# Schematic.net
KiCad netlist of a schematic drawn in Altium Designer
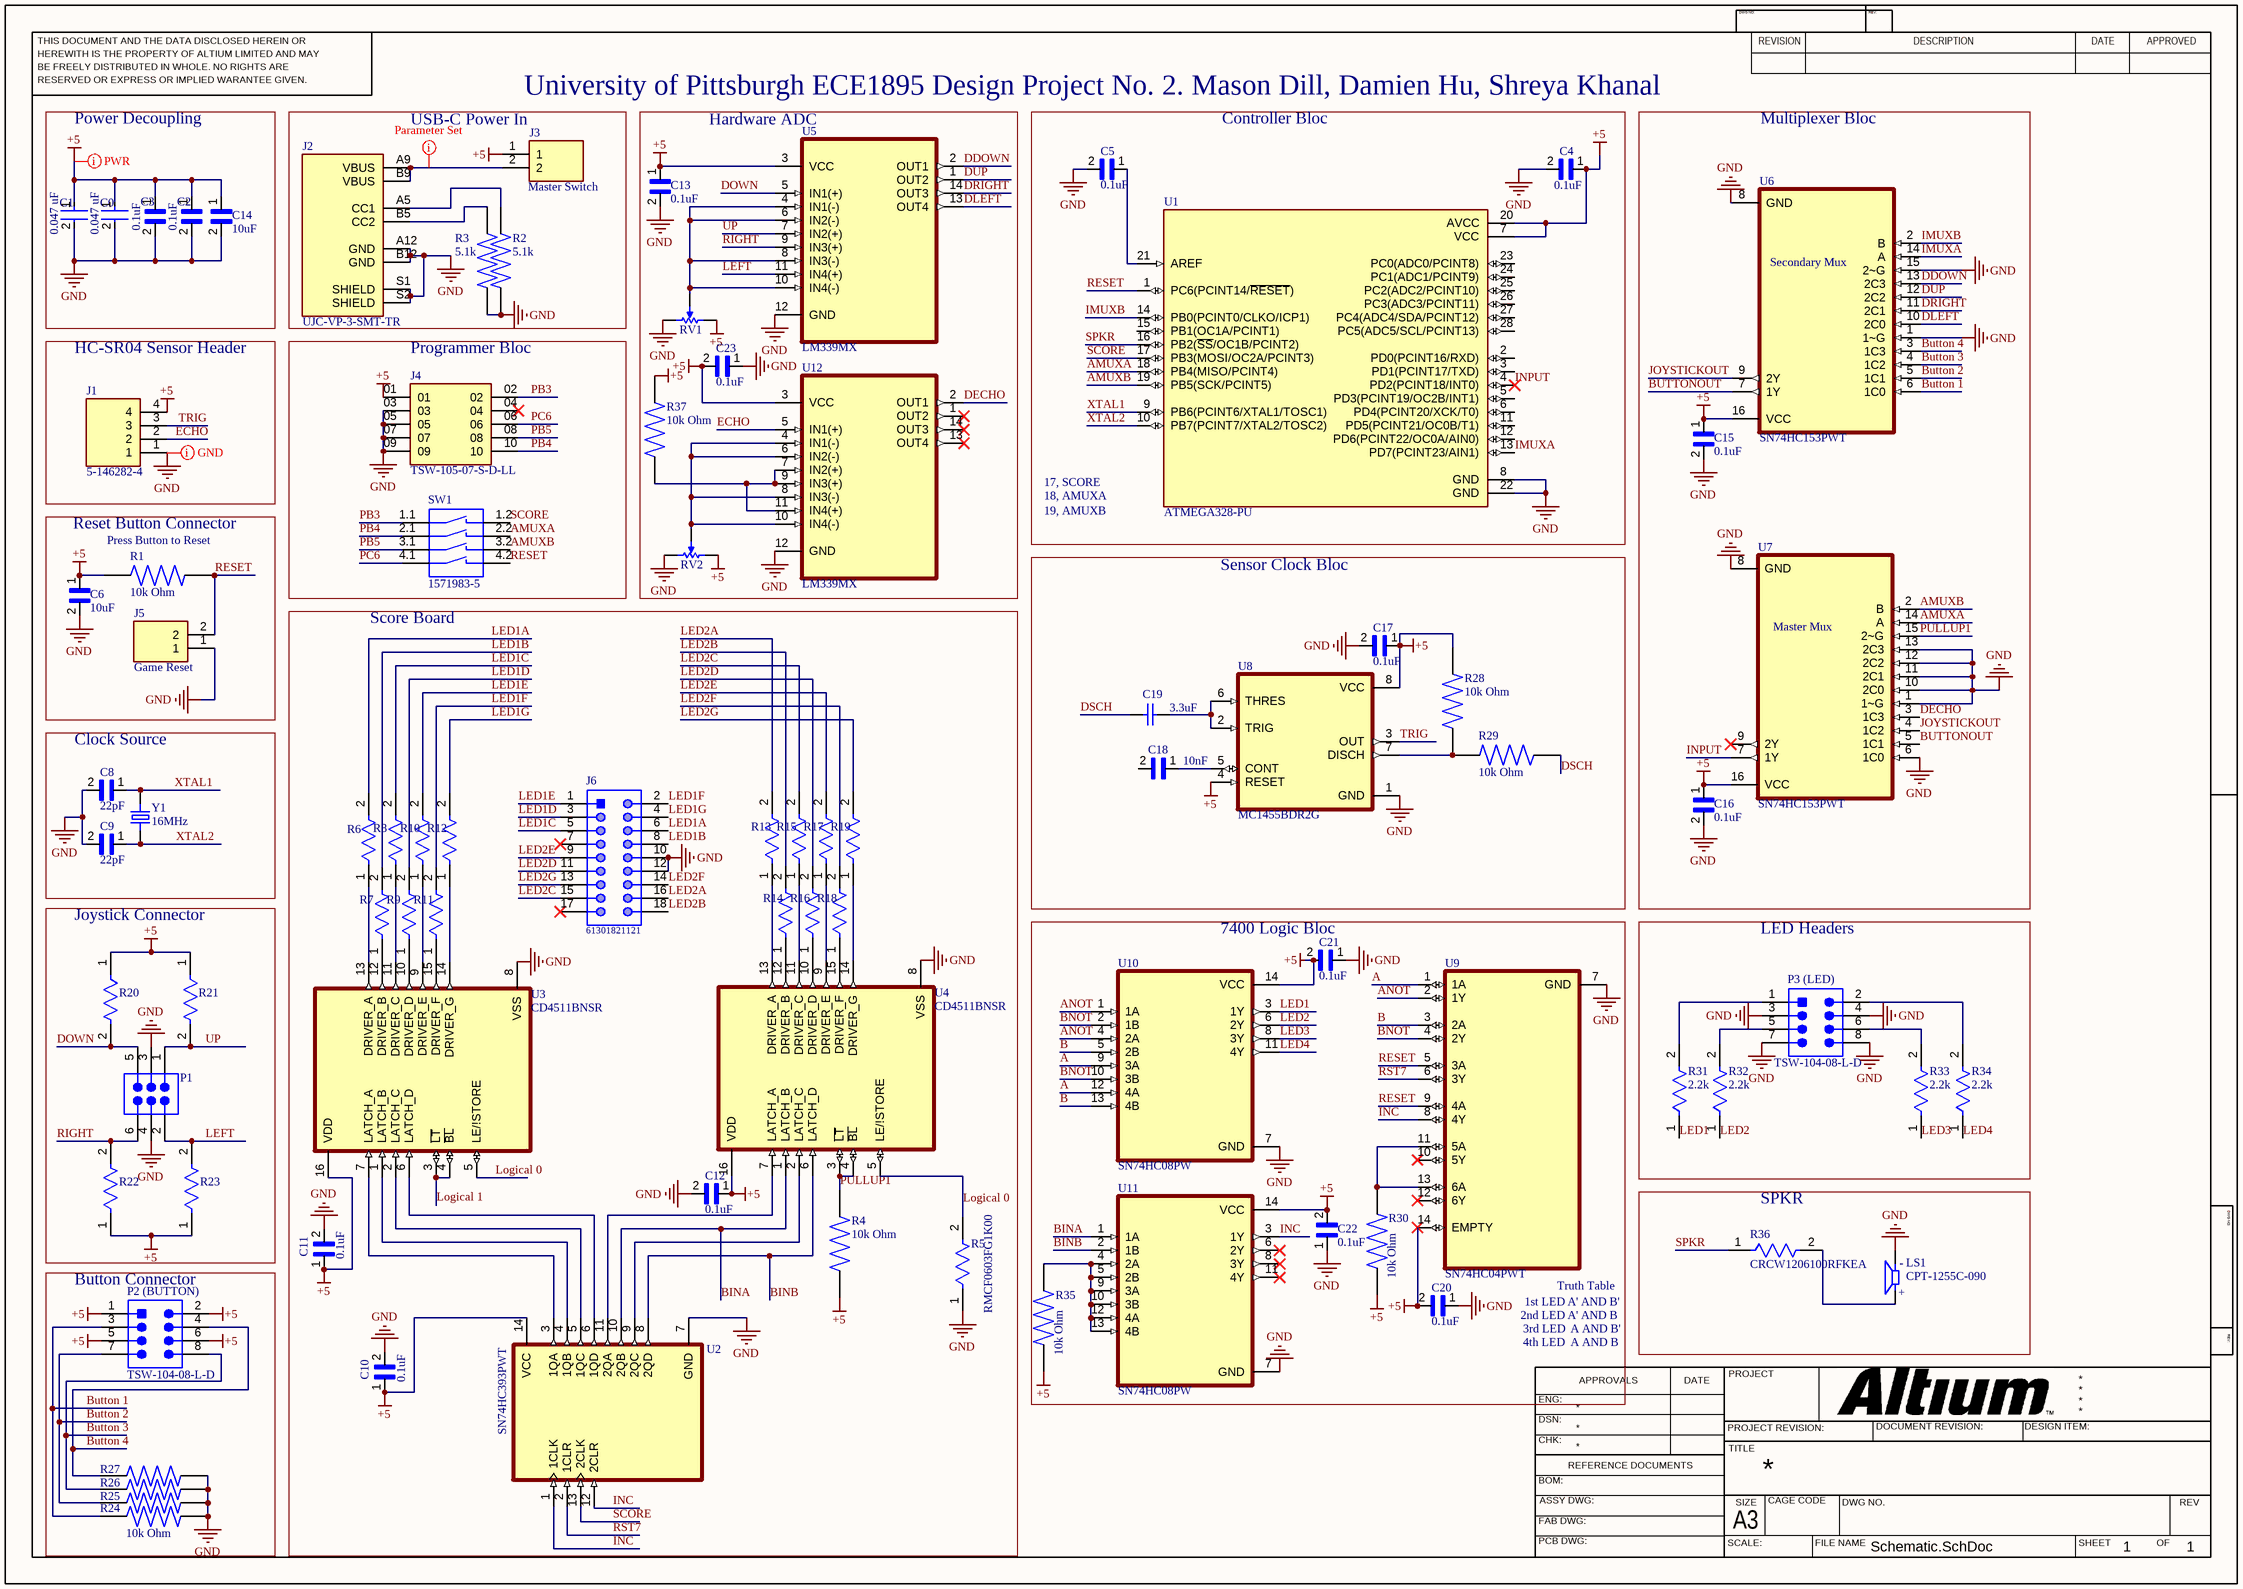
[diagram p0: Schematic.SchDoc]

(export (version "E")
  (design (tool "Eeschema 10.0.6"))
  (components
    (comp (ref "C0")
      (value "0.047 uF")
      (footprint "FP-C0603C-CF-MFG")
      (description "CAP CER 0.047UF 100V 5% X7R 0603")
      (fields
        (field (name "OCTOPART") "https://octopart.com/c0603c473j1ractu-kemet-17301356")
        (field (name "MANUFACTURER") "KEMET")
      )
      (libsource (lib "Altium Content Vault") (part "b4654b650e69147ec39a6b967a45e02"))
    )
    (comp (ref "C1")
      (value "0.047 uF")
      (footprint "FP-C0603C-CF-MFG")
      (description "CAP CER 0.047UF 100V 5% X7R 0603")
      (fields
        (field (name "OCTOPART") "https://octopart.com/c0603c473j1ractu-kemet-17301356")
        (field (name "MANUFACTURER") "KEMET")
      )
      (libsource (lib "Altium Content Vault") (part "b4654b650e69147ec39a6b967a45e02"))
    )
    (comp (ref "C2")
      (value "0.1uF")
      (footprint "CAPC1608X90N")
      (description "0.1ÂµF Â±10% 16V Ceramic Capacitor X7R 0603 _1608 Metric_")
      (fields (field (name "MF") "Taiyo Yuden") (field (name "DIGI-KEY_PART_NUMBER") "587-6004-1-ND"))
      (libsource (lib "") (part "EMK107B7104KAHT_1"))
    )
    (comp (ref "C3")
      (value "0.1uF")
      (footprint "CAPC1608X90N")
      (description "0.1ÂµF Â±10% 16V Ceramic Capacitor X7R 0603 _1608 Metric_")
      (fields (field (name "MF") "Taiyo Yuden") (field (name "DIGI-KEY_PART_NUMBER") "587-6004-1-ND"))
      (libsource (lib "") (part "EMK107B7104KAHT_1"))
    )
    (comp (ref "C4")
      (value "0.1uF")
      (footprint "CAPC1608X90N")
      (description "0.1ÂµF Â±10% 16V Ceramic Capacitor X7R 0603 _1608 Metric_")
      (fields (field (name "MF") "Taiyo Yuden") (field (name "DIGI-KEY_PART_NUMBER") "587-6004-1-ND"))
      (libsource (lib "EMK107B7104KAHT") (part "EMK107B7104KAHT"))
    )
    (comp (ref "C5")
      (value "0.1uF")
      (footprint "CAPC1608X90N")
      (description "0.1ÂµF Â±10% 16V Ceramic Capacitor X7R 0603 _1608 Metric_")
      (fields (field (name "MF") "Taiyo Yuden") (field (name "DIGI-KEY_PART_NUMBER") "587-6004-1-ND"))
      (libsource (lib "EMK107B7104KAHT") (part "EMK107B7104KAHT"))
    )
    (comp (ref "C6")
      (value "10uF")
      (footprint "CAPC1608X90N")
      (description "10 ÂµF Â±10% 10V Ceramic Capacitor JB 0603 (1608 Metric)")
      (fields (field (name "MP") "C1608JB1A106K080AC") (field (name "DIGI-KEY_PART_NUMBER") "445-11201-2-ND"))
      (libsource (lib "C1608JB1A106K080AC") (part "C1608JB1A106K080AC"))
    )
    (comp (ref "C8")
      (value "22pF")
      (footprint "CAPC1608X90N")
      (description "22pF Â±5% 25V Ceramic Capacitor C0G, NP0 0603 _1608 Metric_")
      (fields (field (name "MF") "KEMET") (field (name "MP") "C0603C220J3GACAUTO"))
      (libsource (lib "C0603C220J3GACAUTO") (part "C0603C220J3GACAUTO"))
    )
    (comp (ref "C9")
      (value "22pF")
      (footprint "CAPC1608X90N")
      (description "22pF Â±5% 25V Ceramic Capacitor C0G, NP0 0603 _1608 Metric_")
      (fields (field (name "MF") "KEMET") (field (name "MP") "C0603C220J3GACAUTO"))
      (libsource (lib "C0603C220J3GACAUTO") (part "C0603C220J3GACAUTO"))
    )
    (comp (ref "C10")
      (value "0.1uF")
      (footprint "CAPC1608X90N")
      (description "0.1ÂµF Â±10% 16V Ceramic Capacitor X7R 0603 _1608 Metric_")
      (fields (field (name "MF") "Taiyo Yuden") (field (name "DIGI-KEY_PART_NUMBER") "587-6004-1-ND"))
      (libsource (lib "") (part "EMK107B7104KAHT_2"))
    )
    (comp (ref "C11")
      (value "0.1uF")
      (footprint "CAPC1608X90N")
      (description "0.1ÂµF Â±10% 16V Ceramic Capacitor X7R 0603 _1608 Metric_")
      (fields (field (name "MF") "Taiyo Yuden") (field (name "DIGI-KEY_PART_NUMBER") "587-6004-1-ND"))
      (libsource (lib "") (part "EMK107B7104KAHT_2"))
    )
    (comp (ref "C12")
      (value "0.1uF")
      (footprint "CAPC1608X90N")
      (description "0.1ÂµF Â±10% 16V Ceramic Capacitor X7R 0603 _1608 Metric_")
      (fields (field (name "MF") "Taiyo Yuden") (field (name "DIGI-KEY_PART_NUMBER") "587-6004-1-ND"))
      (libsource (lib "EMK107B7104KAHT") (part "EMK107B7104KAHT"))
    )
    (comp (ref "C13")
      (value "0.1uF")
      (footprint "CAPC1608X90N")
      (description "0.1ÂµF Â±10% 16V Ceramic Capacitor X7R 0603 _1608 Metric_")
      (fields (field (name "MF") "Taiyo Yuden") (field (name "DIGI-KEY_PART_NUMBER") "587-6004-1-ND"))
      (libsource (lib "") (part "EMK107B7104KAHT_1"))
    )
    (comp (ref "C14")
      (value "10uF")
      (footprint "CAPC1608X90N")
      (description "10 ÂµF Â±10% 10V Ceramic Capacitor JB 0603 (1608 Metric)")
      (fields (field (name "MP") "C1608JB1A106K080AC") (field (name "DIGI-KEY_PART_NUMBER") "445-11201-2-ND"))
      (libsource (lib "C1608JB1A106K080AC") (part "C1608JB1A106K080AC"))
    )
    (comp (ref "C15")
      (value "0.1uF")
      (footprint "CAPC1608X90N")
      (description "0.1ÂµF Â±10% 16V Ceramic Capacitor X7R 0603 _1608 Metric_")
      (fields (field (name "MF") "Taiyo Yuden") (field (name "DIGI-KEY_PART_NUMBER") "587-6004-1-ND"))
      (libsource (lib "") (part "EMK107B7104KAHT_1"))
    )
    (comp (ref "C16")
      (value "0.1uF")
      (footprint "CAPC1608X90N")
      (description "0.1ÂµF Â±10% 16V Ceramic Capacitor X7R 0603 _1608 Metric_")
      (fields (field (name "MF") "Taiyo Yuden") (field (name "DIGI-KEY_PART_NUMBER") "587-6004-1-ND"))
      (libsource (lib "") (part "EMK107B7104KAHT_1"))
    )
    (comp (ref "C17")
      (value "0.1uF")
      (footprint "CAPC1608X90N")
      (description "0.1ÂµF Â±10% 16V Ceramic Capacitor X7R 0603 _1608 Metric_")
      (fields (field (name "MF") "Taiyo Yuden") (field (name "DIGI-KEY_PART_NUMBER") "587-6004-1-ND"))
      (libsource (lib "EMK107B7104KAHT") (part "EMK107B7104KAHT"))
    )
    (comp (ref "C18")
      (value "10nF")
      (footprint "CAPC2012X88N")
      (fields (field (name "MP") "C0805C103K1RECAUTO"))
      (libsource (lib "C0805C103K1RECAUTO") (part "C0805C103K1RECAUTO"))
    )
    (comp (ref "C19")
      (value "3.3uF")
      (footprint "CAPC1608X90X35NL15T15")
      (fields (field (name "PART NUMBER") "C0603C335M9PACTU") (field (name "MANUFACTURER") "Kemet"))
      (libsource (lib "Altium Content Vault") (part "CAP"))
    )
    (comp (ref "C20")
      (value "0.1uF")
      (footprint "CAPC1608X90N")
      (description "0.1ÂµF Â±10% 16V Ceramic Capacitor X7R 0603 _1608 Metric_")
      (fields (field (name "MF") "Taiyo Yuden") (field (name "DIGI-KEY_PART_NUMBER") "587-6004-1-ND"))
      (libsource (lib "EMK107B7104KAHT") (part "EMK107B7104KAHT"))
    )
    (comp (ref "C21")
      (value "0.1uF")
      (footprint "CAPC1608X90N")
      (description "0.1ÂµF Â±10% 16V Ceramic Capacitor X7R 0603 _1608 Metric_")
      (fields (field (name "MF") "Taiyo Yuden") (field (name "DIGI-KEY_PART_NUMBER") "587-6004-1-ND"))
      (libsource (lib "EMK107B7104KAHT") (part "EMK107B7104KAHT"))
    )
    (comp (ref "C22")
      (value "0.1uF")
      (footprint "CAPC1608X90N")
      (description "0.1ÂµF Â±10% 16V Ceramic Capacitor X7R 0603 _1608 Metric_")
      (fields (field (name "MF") "Taiyo Yuden") (field (name "DIGI-KEY_PART_NUMBER") "587-6004-1-ND"))
      (libsource (lib "") (part "EMK107B7104KAHT_2"))
    )
    (comp (ref "C23")
      (value "0.1uF")
      (footprint "CAPC1608X90N")
      (description "0.1ÂµF Â±10% 16V Ceramic Capacitor X7R 0603 _1608 Metric_")
      (fields (field (name "MF") "Taiyo Yuden") (field (name "DIGI-KEY_PART_NUMBER") "587-6004-1-ND"))
      (libsource (lib "EMK107B7104KAHT") (part "EMK107B7104KAHT"))
    )
    (comp (ref "J1")
      (value "5-146282-4")
      (footprint "TE_5-146282-4")
      (description "Connector Header Through Hole 4 position 0.100 (2.54mm)")
      (fields (field (name "MF") "TE Connectivity"))
      (libsource (lib "5-146282-4") (part "5-146282-4"))
    )
    (comp (ref "J2")
      (value "UJC-VP-3-SMT-TR")
      (footprint "CUI_UJC-VP-3-SMT-TR")
      (description "USB Receptacle")
      (fields (field (name "MF") "{'manufacturer': u'CUI'}"))
      (libsource (lib "UJC-VP-3-SMT-TR") (part "UJC-VP-3-SMT-TR"))
    )
    (comp (ref "J3")
      (value "Master Switch")
      (footprint "CUI_TB003-500-P02BE")
      (description "2~24 Poles, Screw Type, Horizontal, 5.0 Pitch, 26~14 _AWG_, Terminal Block Connector")
      (fields (field (name "MP") "TB003-500-P02BE") (field (name "MF") "CUI Devices"))
      (libsource (lib "TB003-500-P02BE") (part "TB003-500-P02BE"))
    )
    (comp (ref "J4")
      (value "TSW-105-07-S-D-LL")
      (footprint "SAMTEC_TSW-105-07-S-D-LL")
      (libsource (lib "TSW-105-07-S-D-LL") (part "TSW-105-07-S-D-LL"))
    )
    (comp (ref "J5")
      (value "Game Reset")
      (footprint "CUI_TB003-500-P02BE")
      (description "2~24 Poles, Screw Type, Horizontal, 5.0 Pitch, 26~14 _AWG_, Terminal Block Connector")
      (fields (field (name "MP") "TB003-500-P02BE") (field (name "MF") "CUI Devices"))
      (libsource (lib "") (part "TB003-500-P02BE_1"))
    )
    (comp (ref "J6")
      (value "61301821121")
      (footprint "61301821121")
      (description "THT Vertical Pin Header WR-PHD, Pitch 2.54 mm, Dual Row, 18 pins")
      (fields (field (name "MANUFACTURER") "Wurth Elektronik") (field (name "PUBLISHER") "WurthElektronik"))
      (libsource (lib "Altium Content Vault") (part "WE-CN-2P-M-R18"))
    )
    (comp (ref "LS1")
      (value "CPT-1255C-090")
      (footprint "CUI_CPT-1255C-090")
      (description "12 mm, 20 Vp-p, 80 dB, Through Hole, Piezo Audio Transducer Buzzer")
      (fields (field (name "MF") "CUI Devices"))
      (libsource (lib "CPT-1255C-090") (part "CPT-1255C-090"))
    )
    (comp (ref "P1")
      (value "TSW-103-08-G-D")
      (footprint "SMTC-TSW-103-08-X-D")
      (description "0.025\" SQ Post Header, Through-hole, Vertical, -55 to 125 degC, 2.54 mm Pitch, 6-Pin, Male, RoHS")
      (fields (field (name "MANUFACTURER") "Samtec"))
      (libsource (lib "Altium Content Vault") (part "SMTC-TSW-103-08-X-D"))
    )
    (comp (ref "P2 (BUTTON)")
      (value "TSW-104-08-L-D")
      (footprint "SMTC-TSW-104-08-L-D_V")
      (fields (field (name "MANUFACTURER") "Samtec"))
      (libsource (lib "Altium Content Vault") (part "CN-2P-M-R8"))
    )
    (comp (ref "P3 (LED)")
      (value "TSW-104-08-L-D")
      (footprint "SMTC-TSW-104-08-L-D_V")
      (fields (field (name "MANUFACTURER") "Samtec"))
      (libsource (lib "Altium Content Vault") (part "CN-2P-M-R8"))
    )
    (comp (ref "R1")
      (value "10k Ohm")
      (footprint "RESC3116X60N")
      (fields (field (name "MP") "CRCW120610K0DHEAP"))
      (libsource (lib "CRCW120610K0DHEAP") (part "CRCW120610K0DHEAP"))
    )
    (comp (ref "R2")
      (value "5.1k")
      (footprint "RESC6332X120N")
      (description "Res Thick Film 2512 5.1K Ohm 1% 3W SMD T/R")
      (fields (field (name "MP") "35225K1FT"))
      (libsource (lib "35225K1FT") (part "35225K1FT"))
    )
    (comp (ref "R3")
      (value "5.1k")
      (footprint "RESC6332X120N")
      (description "Res Thick Film 2512 5.1K Ohm 1% 3W SMD T/R")
      (fields (field (name "MP") "35225K1FT"))
      (libsource (lib "35225K1FT") (part "35225K1FT"))
    )
    (comp (ref "R4")
      (value "10k Ohm")
      (footprint "RESC3116X60N")
      (fields (field (name "MP") "CRCW120610K0DHEAP"))
      (libsource (lib "CRCW120610K0DHEAP") (part "CRCW120610K0DHEAP"))
    )
    (comp (ref "R5")
      (value "RMCF0603FG1K00")
      (footprint "FP-RMCF0603-IPC_B")
      (description "1kΩ ±1% 0.1W 0603 Thick Film Chip Resistor AEC-Q200 compliant")
      (fields (field (name "TOLERANCE") "1%"))
      (libsource (lib "Altium Content Vault") (part "1029c3af85768c4190bb7ad29bc67b5"))
    )
    (comp (ref "R6")
      (value "100 Ohm")
      (footprint "FP-CRCW1206-e3-MFG")
      (description "RES Thick Film, 100Ω, 1%, 0.25W, 100ppm/°C, 1206")
      (fields (field (name "TOLERANCE") "1%"))
      (libsource (lib "Altium Content Vault") (part "1029c3af85768c4190bb7ad29bc67b5"))
    )
    (comp (ref "R7")
      (value "100 Ohm")
      (footprint "FP-CRCW1206-e3-MFG")
      (description "RES Thick Film, 100Ω, 1%, 0.25W, 100ppm/°C, 1206")
      (fields (field (name "TOLERANCE") "1%"))
      (libsource (lib "Altium Content Vault") (part "1029c3af85768c4190bb7ad29bc67b5"))
    )
    (comp (ref "R8")
      (value "100 Ohm")
      (footprint "FP-CRCW1206-e3-MFG")
      (description "RES Thick Film, 100Ω, 1%, 0.25W, 100ppm/°C, 1206")
      (fields (field (name "TOLERANCE") "1%"))
      (libsource (lib "Altium Content Vault") (part "1029c3af85768c4190bb7ad29bc67b5"))
    )
    (comp (ref "R9")
      (value "100 Ohm")
      (footprint "FP-CRCW1206-e3-MFG")
      (description "RES Thick Film, 100Ω, 1%, 0.25W, 100ppm/°C, 1206")
      (fields (field (name "TOLERANCE") "1%"))
      (libsource (lib "Altium Content Vault") (part "1029c3af85768c4190bb7ad29bc67b5"))
    )
    (comp (ref "R10")
      (value "100 Ohm")
      (footprint "FP-CRCW1206-e3-MFG")
      (description "RES Thick Film, 100Ω, 1%, 0.25W, 100ppm/°C, 1206")
      (fields (field (name "TOLERANCE") "1%"))
      (libsource (lib "Altium Content Vault") (part "1029c3af85768c4190bb7ad29bc67b5"))
    )
    (comp (ref "R11")
      (value "100 Ohm")
      (footprint "FP-CRCW1206-e3-MFG")
      (description "RES Thick Film, 100Ω, 1%, 0.25W, 100ppm/°C, 1206")
      (fields (field (name "TOLERANCE") "1%"))
      (libsource (lib "Altium Content Vault") (part "1029c3af85768c4190bb7ad29bc67b5"))
    )
    (comp (ref "R12")
      (value "100 Ohm")
      (footprint "FP-CRCW1206-e3-MFG")
      (description "RES Thick Film, 100Ω, 1%, 0.25W, 100ppm/°C, 1206")
      (fields (field (name "TOLERANCE") "1%"))
      (libsource (lib "Altium Content Vault") (part "1029c3af85768c4190bb7ad29bc67b5"))
    )
    (comp (ref "R13")
      (value "100 Ohm")
      (footprint "FP-CRCW1206-e3-MFG")
      (description "RES Thick Film, 100Ω, 1%, 0.25W, 100ppm/°C, 1206")
      (fields (field (name "TOLERANCE") "1%"))
      (libsource (lib "Altium Content Vault") (part "1029c3af85768c4190bb7ad29bc67b5"))
    )
    (comp (ref "R14")
      (value "100 Ohm")
      (footprint "FP-CRCW1206-e3-MFG")
      (description "RES Thick Film, 100Ω, 1%, 0.25W, 100ppm/°C, 1206")
      (fields (field (name "TOLERANCE") "1%"))
      (libsource (lib "Altium Content Vault") (part "1029c3af85768c4190bb7ad29bc67b5"))
    )
    (comp (ref "R15")
      (value "100 Ohm")
      (footprint "FP-CRCW1206-e3-MFG")
      (description "RES Thick Film, 100Ω, 1%, 0.25W, 100ppm/°C, 1206")
      (fields (field (name "TOLERANCE") "1%"))
      (libsource (lib "Altium Content Vault") (part "1029c3af85768c4190bb7ad29bc67b5"))
    )
    (comp (ref "R16")
      (value "100 Ohm")
      (footprint "FP-CRCW1206-e3-MFG")
      (description "RES Thick Film, 100Ω, 1%, 0.25W, 100ppm/°C, 1206")
      (fields (field (name "TOLERANCE") "1%"))
      (libsource (lib "Altium Content Vault") (part "1029c3af85768c4190bb7ad29bc67b5"))
    )
    (comp (ref "R17")
      (value "100 Ohm")
      (footprint "FP-CRCW1206-e3-MFG")
      (description "RES Thick Film, 100Ω, 1%, 0.25W, 100ppm/°C, 1206")
      (fields (field (name "TOLERANCE") "1%"))
      (libsource (lib "Altium Content Vault") (part "1029c3af85768c4190bb7ad29bc67b5"))
    )
    (comp (ref "R18")
      (value "100 Ohm")
      (footprint "FP-CRCW1206-e3-MFG")
      (description "RES Thick Film, 100Ω, 1%, 0.25W, 100ppm/°C, 1206")
      (fields (field (name "TOLERANCE") "1%"))
      (libsource (lib "Altium Content Vault") (part "1029c3af85768c4190bb7ad29bc67b5"))
    )
    (comp (ref "R19")
      (value "100 Ohm")
      (footprint "FP-CRCW1206-e3-MFG")
      (description "RES Thick Film, 100Ω, 1%, 0.25W, 100ppm/°C, 1206")
      (fields (field (name "TOLERANCE") "1%"))
      (libsource (lib "Altium Content Vault") (part "1029c3af85768c4190bb7ad29bc67b5"))
    )
    (comp (ref "R20")
      (value "CRCW12062K20FKEA")
      (footprint "FP-CRCW1206-e3-IPC_C")
      (description "RES Thick Film, 2.2kΩ, 1%, 0.25W, 100ppm/°C, 1206")
      (fields (field (name "TOLERANCE") "1%"))
      (libsource (lib "Altium Content Vault") (part "1029c3af85768c4190bb7ad29bc67b5"))
    )
    (comp (ref "R21")
      (value "CRCW12062K20FKEA")
      (footprint "FP-CRCW1206-e3-IPC_C")
      (description "RES Thick Film, 2.2kΩ, 1%, 0.25W, 100ppm/°C, 1206")
      (fields (field (name "TOLERANCE") "1%"))
      (libsource (lib "Altium Content Vault") (part "1029c3af85768c4190bb7ad29bc67b5"))
    )
    (comp (ref "R22")
      (value "CRCW12062K20FKEA")
      (footprint "FP-CRCW1206-e3-IPC_C")
      (description "RES Thick Film, 2.2kΩ, 1%, 0.25W, 100ppm/°C, 1206")
      (fields (field (name "TOLERANCE") "1%"))
      (libsource (lib "Altium Content Vault") (part "1029c3af85768c4190bb7ad29bc67b5"))
    )
    (comp (ref "R23")
      (value "CRCW12062K20FKEA")
      (footprint "FP-CRCW1206-e3-IPC_C")
      (description "RES Thick Film, 2.2kΩ, 1%, 0.25W, 100ppm/°C, 1206")
      (fields (field (name "TOLERANCE") "1%"))
      (libsource (lib "Altium Content Vault") (part "1029c3af85768c4190bb7ad29bc67b5"))
    )
    (comp (ref "R24")
      (value "10k Ohm")
      (footprint "RESC3116X60N")
      (fields (field (name "MP") "CRCW120610K0DHEAP"))
      (libsource (lib "CRCW120610K0DHEAP") (part "CRCW120610K0DHEAP"))
    )
    (comp (ref "R25")
      (value "10k Ohm")
      (footprint "RESC3116X60N")
      (fields (field (name "MP") "CRCW120610K0DHEAP"))
      (libsource (lib "CRCW120610K0DHEAP") (part "CRCW120610K0DHEAP"))
    )
    (comp (ref "R26")
      (value "10k Ohm")
      (footprint "RESC3116X60N")
      (fields (field (name "MP") "CRCW120610K0DHEAP"))
      (libsource (lib "CRCW120610K0DHEAP") (part "CRCW120610K0DHEAP"))
    )
    (comp (ref "R27")
      (value "10k Ohm")
      (footprint "RESC3116X60N")
      (fields (field (name "MP") "CRCW120610K0DHEAP"))
      (libsource (lib "CRCW120610K0DHEAP") (part "CRCW120610K0DHEAP"))
    )
    (comp (ref "R28")
      (value "10k Ohm")
      (footprint "RESC3116X60N")
      (fields (field (name "MP") "CRCW120610K0DHEAP"))
      (libsource (lib "CRCW120610K0DHEAP") (part "CRCW120610K0DHEAP"))
    )
    (comp (ref "R29")
      (value "10k Ohm")
      (footprint "RESC3116X60N")
      (fields (field (name "MP") "CRCW120610K0DHEAP"))
      (libsource (lib "CRCW120610K0DHEAP") (part "CRCW120610K0DHEAP"))
    )
    (comp (ref "R30")
      (value "10k Ohm")
      (footprint "RESC3116X60N")
      (fields (field (name "MP") "CRCW120610K0DHEAP"))
      (libsource (lib "CRCW120610K0DHEAP") (part "CRCW120610K0DHEAP"))
    )
    (comp (ref "R31")
      (value "2.2k")
      (footprint "FP-CRCW1206-e3-IPC_C")
      (description "RES Thick Film, 2.2kΩ, 1%, 0.25W, 100ppm/°C, 1206")
      (fields (field (name "TOLERANCE") "1%"))
      (libsource (lib "Altium Content Vault") (part "1029c3af85768c4190bb7ad29bc67b5"))
    )
    (comp (ref "R32")
      (value "2.2k")
      (footprint "FP-CRCW1206-e3-IPC_C")
      (description "RES Thick Film, 2.2kΩ, 1%, 0.25W, 100ppm/°C, 1206")
      (fields (field (name "TOLERANCE") "1%"))
      (libsource (lib "Altium Content Vault") (part "1029c3af85768c4190bb7ad29bc67b5"))
    )
    (comp (ref "R33")
      (value "2.2k")
      (footprint "FP-CRCW1206-e3-IPC_C")
      (description "RES Thick Film, 2.2kΩ, 1%, 0.25W, 100ppm/°C, 1206")
      (fields (field (name "TOLERANCE") "1%"))
      (libsource (lib "Altium Content Vault") (part "1029c3af85768c4190bb7ad29bc67b5"))
    )
    (comp (ref "R34")
      (value "2.2k")
      (footprint "FP-CRCW1206-e3-IPC_C")
      (description "RES Thick Film, 2.2kΩ, 1%, 0.25W, 100ppm/°C, 1206")
      (fields (field (name "TOLERANCE") "1%"))
      (libsource (lib "Altium Content Vault") (part "1029c3af85768c4190bb7ad29bc67b5"))
    )
    (comp (ref "R35")
      (value "10k Ohm")
      (footprint "RESC3116X60N")
      (fields (field (name "MP") "CRCW120610K0DHEAP"))
      (libsource (lib "CRCW120610K0DHEAP") (part "CRCW120610K0DHEAP"))
    )
    (comp (ref "R36")
      (value "CRCW1206100RFKEA")
      (footprint "FP-CRCW1206-e3-MFG")
      (description "RES Thick Film, 100Ω, 1%, 0.25W, 100ppm/°C, 1206")
      (fields (field (name "TOLERANCE") "1%"))
      (libsource (lib "Altium Content Vault") (part "1029c3af85768c4190bb7ad29bc67b5"))
    )
    (comp (ref "R37")
      (value "10k Ohm")
      (footprint "RESC3116X60N")
      (fields (field (name "MP") "CRCW120610K0DHEAP"))
      (libsource (lib "CRCW120610K0DHEAP") (part "CRCW120610K0DHEAP"))
    )
    (comp (ref "RV1")
      (value "3290W-1-203")
      (footprint "BOUR-3290W")
      (description "Trimming Potentiometer, 20 KOhm, 1 W, -65 to 150 degC, 3-Pin THD, RoHS, Tube")
      (fields (field (name "MANUFACTURER") "Bourns"))
      (libsource (lib "Altium Content Vault") (part "RES-ADJ-3_A"))
    )
    (comp (ref "RV2")
      (value "3290W-1-203")
      (footprint "BOUR-3290W")
      (description "Trimming Potentiometer, 20 KOhm, 1 W, -65 to 150 degC, 3-Pin THD, RoHS, Tube")
      (fields (field (name "MANUFACTURER") "Bourns"))
      (libsource (lib "Altium Content Vault") (part "RES-ADJ-3_A"))
    )
    (comp (ref "SW1")
      (value "1571983-5")
      (footprint "SW_1571983-5")
      (description "GDH04STR04=DIP SWITCH")
      (fields (field (name "DIGI-KEY_PART_NUMBER") "450-1762-1-ND") (field (name "MF") "TE Connectivity"))
      (libsource (lib "1571983-5") (part "1571983-5"))
    )
    (comp (ref "U1")
      (value "ATMEGA328-PU")
      (footprint "DIP787W46P254L3467H508Q28")
      (description "AVR AVRÂ® ATmega Microcontroller IC 8-Bit 20MHz 32KB (16K x 16) FLASH 28-PDIP")
      (fields (field (name "MF") "Microchip Technology"))
      (libsource (lib "ATMEGA328-PU") (part "ATMEGA328-PU"))
    )
    (comp (ref "U2")
      (value "SN74HC393PWT")
      (footprint "SOP65P640X120-14N")
      (libsource (lib "SN74HC393PWT") (part "SN74HC393PWT"))
    )
    (comp (ref "U3")
      (value "CD4511BNSR")
      (footprint "SOP127P780X200-16N")
      (libsource (lib "CD4511BNSR") (part "CD4511BNSR"))
    )
    (comp (ref "U4")
      (value "CD4511BNSR")
      (footprint "SOP127P780X200-16N")
      (libsource (lib "CD4511BNSR") (part "CD4511BNSR"))
    )
    (comp (ref "U5")
      (value "LM339MX")
      (footprint "SOIC127P630X170-14N")
      (description "Quad Comparator")
      (libsource (lib "LM339MX") (part "LM339MX"))
    )
    (comp (ref "U6")
      (value "SN74HC153PWT")
      (footprint "SOP65P640X120-16N")
      (description "IC MULTIPLEXER 2 X 4:1 16TSSOP")
      (fields (field (name "MP") "SN74HC153N") (field (name "MF") "Texas Instruments"))
      (libsource (lib "SN74HC153N") (part "SN74HC153N"))
    )
    (comp (ref "U7")
      (value "SN74HC153PWT")
      (footprint "SOP65P640X120-16N")
      (description "IC MULTIPLEXER 2 X 4:1 16TSSOP")
      (fields (field (name "MP") "SN74HC153N") (field (name "MF") "Texas Instruments"))
      (libsource (lib "SN74HC153N") (part "SN74HC153N"))
    )
    (comp (ref "U8")
      (value "MC1455BDR2G")
      (footprint "SOIC127P599X175-8N")
      (description "Single Precision Timer")
      (fields (field (name "MP") "NE555DR") (field (name "MF") "Texas Instruments"))
      (libsource (lib "NE555DR") (part "NE555DR"))
    )
    (comp (ref "U9")
      (value "SN74HC04PWT")
      (footprint "SOP65P640X120-14N")
      (description "Hex Inverters 14-TSSOP -40 to 85")
      (fields
        (field (name "DIGI-KEY_PART_NUMBER") "296-SN74HC04PWTTR-ND")
        (field (name "MF") "Texas Instruments")
      )
      (libsource (lib "SN74HC04PWT") (part "SN74HC04PWT"))
    )
    (comp (ref "U10")
      (value "SN74HC08PW")
      (footprint "SOP65P640X120-14N")
      (libsource (lib "SN74HC08PW") (part "SN74HC08PW"))
    )
    (comp (ref "U11")
      (value "SN74HC08PW")
      (footprint "SOP65P640X120-14N")
      (libsource (lib "SN74HC08PW") (part "SN74HC08PW"))
    )
    (comp (ref "U12")
      (value "LM339MX")
      (footprint "SOIC127P630X170-14N")
      (description "Quad Comparator")
      (libsource (lib "LM339MX") (part "LM339MX"))
    )
    (comp (ref "Y1")
      (value "16MHz")
      (footprint "XTAL_ECS-160-20-23A-EN-TR")
      (description "16MHz Â±30ppm Crystal 20pF 60 Ohms 2-SMD, No Lead")
      (fields (field (name "MP") "ECS-160-20-23A-EN-TR") (field (name "DIGI-KEY_PART_NUMBER") "XC982CT-ND"))
      (libsource (lib "ECS-160-20-23A-EN-TR") (part "ECS-160-20-23A-EN-TR"))
    )
  )
  (nets
    (net (code "1") (name "+5") (class "Default")
      (node (ref "C0") (pin "1") (pinfunction "1_1") (pintype "passive"))
      (node (ref "C1") (pin "1") (pinfunction "1_1") (pintype "passive"))
      (node (ref "C10") (pin "1") (pinfunction "1_1") (pintype "passive"))
      (node (ref "C11") (pin "1") (pinfunction "1_1") (pintype "passive"))
      (node (ref "C12") (pin "1") (pinfunction "1_1") (pintype "passive"))
      (node (ref "C13") (pin "1") (pinfunction "1_1") (pintype "passive"))
      (node (ref "C14") (pin "1") (pinfunction "1_1") (pintype "passive"))
      (node (ref "C15") (pin "1") (pinfunction "1_1") (pintype "passive"))
      (node (ref "C16") (pin "1") (pinfunction "1_1") (pintype "passive"))
      (node (ref "C17") (pin "1") (pinfunction "1_1") (pintype "passive"))
      (node (ref "C2") (pin "1") (pinfunction "1_1") (pintype "passive"))
      (node (ref "C20") (pin "2") (pinfunction "2_2") (pintype "passive"))
      (node (ref "C21") (pin "2") (pinfunction "2_2") (pintype "passive"))
      (node (ref "C22") (pin "2") (pinfunction "2_2") (pintype "passive"))
      (node (ref "C23") (pin "2") (pinfunction "2_2") (pintype "passive"))
      (node (ref "C3") (pin "1") (pinfunction "1_1") (pintype "passive"))
      (node (ref "C4") (pin "1") (pinfunction "1_1") (pintype "passive"))
      (node (ref "C6") (pin "1") (pinfunction "1_1") (pintype "passive"))
      (node (ref "J1") (pin "4") (pinfunction "4_4") (pintype "passive"))
      (node (ref "J3") (pin "1") (pinfunction "1_1") (pintype "passive"))
      (node (ref "J4") (pin "01") (pinfunction "01_01") (pintype "passive"))
      (node (ref "P2 (BUTTON)") (pin "1") (pinfunction "1_1") (pintype "passive"))
      (node (ref "P2 (BUTTON)") (pin "2") (pinfunction "2_2") (pintype "passive"))
      (node (ref "P2 (BUTTON)") (pin "5") (pinfunction "5_5") (pintype "passive"))
      (node (ref "P2 (BUTTON)") (pin "6") (pinfunction "6_6") (pintype "passive"))
      (node (ref "R1") (pin "1") (pinfunction "1_1") (pintype "passive"))
      (node (ref "R20") (pin "1") (pinfunction "1_1") (pintype "passive"))
      (node (ref "R21") (pin "1") (pinfunction "1_1") (pintype "passive"))
      (node (ref "R22") (pin "1") (pinfunction "1_1") (pintype "passive"))
      (node (ref "R23") (pin "1") (pinfunction "1_1") (pintype "passive"))
      (node (ref "R28") (pin "2") (pinfunction "2_2") (pintype "passive"))
      (node (ref "R30") (pin "2") (pinfunction "2_2") (pintype "passive"))
      (node (ref "R35") (pin "2") (pinfunction "2_2") (pintype "passive"))
      (node (ref "R37") (pin "2") (pinfunction "2_2") (pintype "passive"))
      (node (ref "R4") (pin "1") (pinfunction "1_1") (pintype "passive"))
      (node (ref "RV1") (pin "1") (pinfunction "1_1") (pintype "passive"))
      (node (ref "RV2") (pin "1") (pinfunction "1_1") (pintype "passive"))
      (node (ref "U1") (pin "20") (pinfunction "AVCC_20") (pintype "power_in"))
      (node (ref "U1") (pin "7") (pinfunction "VCC_7") (pintype "power_in"))
      (node (ref "U10") (pin "14") (pinfunction "VCC_14") (pintype "power_in"))
      (node (ref "U11") (pin "14") (pinfunction "VCC_14") (pintype "power_in"))
      (node (ref "U12") (pin "3") (pinfunction "VCC_3") (pintype "power_in"))
      (node (ref "U2") (pin "14") (pinfunction "VCC_14") (pintype "power_in"))
      (node (ref "U3") (pin "16") (pinfunction "VDD_16") (pintype "power_in"))
      (node (ref "U4") (pin "16") (pinfunction "VDD_16") (pintype "power_in"))
      (node (ref "U5") (pin "3") (pinfunction "VCC_3") (pintype "power_in"))
      (node (ref "U6") (pin "16") (pinfunction "VCC_16") (pintype "power_in"))
      (node (ref "U7") (pin "16") (pinfunction "VCC_16") (pintype "power_in"))
      (node (ref "U8") (pin "4") (pinfunction "RESET_4") (pintype "input"))
      (node (ref "U8") (pin "8") (pinfunction "VCC_8") (pintype "power_in"))
      (node (ref "U9") (pin "14") (pinfunction "EMPTY_14") (pintype "bidirectional"))
    )
    (net (code "2") (name "/A") (class "Default")
      (node (ref "U10") (pin "12") (pinfunction "4A_12") (pintype "input"))
      (node (ref "U10") (pin "9") (pinfunction "3A_9") (pintype "input"))
      (node (ref "U9") (pin "1") (pinfunction "1A_1") (pintype "bidirectional"))
    )
    (net (code "3") (name "/AMUXA") (class "Default")
      (node (ref "SW1") (pin "2.2") (pinfunction "2.2_2.2") (pintype "passive"))
      (node (ref "U1") (pin "18") (pinfunction "PB4(MISO/PCINT4)_18") (pintype "bidirectional"))
      (node (ref "U7") (pin "14") (pinfunction "A_14") (pintype "input"))
    )
    (net (code "4") (name "/AMUXB") (class "Default")
      (node (ref "SW1") (pin "3.2") (pinfunction "3.2_3.2") (pintype "passive"))
      (node (ref "U1") (pin "19") (pinfunction "PB5(SCK/PCINT5)_19") (pintype "bidirectional"))
      (node (ref "U7") (pin "2") (pinfunction "B_2") (pintype "input"))
    )
    (net (code "5") (name "/ANOT") (class "Default")
      (node (ref "U10") (pin "1") (pinfunction "1A_1") (pintype "input"))
      (node (ref "U10") (pin "4") (pinfunction "2A_4") (pintype "input"))
      (node (ref "U9") (pin "2") (pinfunction "1Y_2") (pintype "bidirectional"))
    )
    (net (code "6") (name "/B") (class "Default")
      (node (ref "U10") (pin "13") (pinfunction "4B_13") (pintype "input"))
      (node (ref "U10") (pin "5") (pinfunction "2B_5") (pintype "input"))
      (node (ref "U9") (pin "3") (pinfunction "2A_3") (pintype "bidirectional"))
    )
    (net (code "7") (name "/BINA") (class "Default")
      (node (ref "U11") (pin "1") (pinfunction "1A_1") (pintype "input"))
      (node (ref "U2") (pin "10") (pinfunction "2QB_10") (pintype "output"))
      (node (ref "U4") (pin "1") (pinfunction "LATCH_B_1") (pintype "input"))
    )
    (net (code "8") (name "/BINB") (class "Default")
      (node (ref "U11") (pin "2") (pinfunction "1B_2") (pintype "input"))
      (node (ref "U2") (pin "8") (pinfunction "2QD_8") (pintype "output"))
      (node (ref "U4") (pin "6") (pinfunction "LATCH_D_6") (pintype "input"))
    )
    (net (code "9") (name "/BNOT") (class "Default")
      (node (ref "U10") (pin "10") (pinfunction "3B_10") (pintype "input"))
      (node (ref "U10") (pin "2") (pinfunction "1B_2") (pintype "input"))
      (node (ref "U9") (pin "4") (pinfunction "2Y_4") (pintype "bidirectional"))
    )
    (net (code "10") (name "/BUTTONOUT") (class "Default")
      (node (ref "U6") (pin "7") (pinfunction "1Y_7") (pintype "output"))
      (node (ref "U7") (pin "5") (pinfunction "1C1_5") (pintype "input"))
    )
    (net (code "11") (name "/Button 1") (class "Default")
      (node (ref "P2 (BUTTON)") (pin "3") (pinfunction "3_3") (pintype "passive"))
      (node (ref "R24") (pin "2") (pinfunction "2_2") (pintype "passive"))
      (node (ref "U6") (pin "6") (pinfunction "1C0_6") (pintype "input"))
    )
    (net (code "12") (name "/Button 2") (class "Default")
      (node (ref "P2 (BUTTON)") (pin "7") (pinfunction "7_7") (pintype "passive"))
      (node (ref "R25") (pin "2") (pinfunction "2_2") (pintype "passive"))
      (node (ref "U6") (pin "5") (pinfunction "1C1_5") (pintype "input"))
    )
    (net (code "13") (name "/Button 3") (class "Default")
      (node (ref "P2 (BUTTON)") (pin "8") (pinfunction "8_8") (pintype "passive"))
      (node (ref "R26") (pin "2") (pinfunction "2_2") (pintype "passive"))
      (node (ref "U6") (pin "4") (pinfunction "1C2_4") (pintype "input"))
    )
    (net (code "14") (name "/Button 4") (class "Default")
      (node (ref "P2 (BUTTON)") (pin "4") (pinfunction "4_4") (pintype "passive"))
      (node (ref "R27") (pin "2") (pinfunction "2_2") (pintype "passive"))
      (node (ref "U6") (pin "3") (pinfunction "1C3_3") (pintype "input"))
    )
    (net (code "15") (name "/DDOWN") (class "Default")
      (node (ref "U5") (pin "2") (pinfunction "OUT1_2") (pintype "output"))
      (node (ref "U6") (pin "13") (pinfunction "2C3_13") (pintype "input"))
    )
    (net (code "16") (name "/DECHO") (class "Default")
      (node (ref "U12") (pin "2") (pinfunction "OUT1_2") (pintype "output"))
      (node (ref "U7") (pin "3") (pinfunction "1C3_3") (pintype "input"))
    )
    (net (code "17") (name "/DLEFT") (class "Default")
      (node (ref "U5") (pin "13") (pinfunction "OUT4_13") (pintype "output"))
      (node (ref "U6") (pin "10") (pinfunction "2C0_10") (pintype "input"))
    )
    (net (code "18") (name "/DOWN") (class "Default")
      (node (ref "P1") (pin "5") (pinfunction "5_5") (pintype "passive"))
      (node (ref "R20") (pin "2") (pinfunction "2_2") (pintype "passive"))
      (node (ref "U5") (pin "5") (pinfunction "IN1(+)_5") (pintype "input"))
    )
    (net (code "19") (name "/DRIGHT") (class "Default")
      (node (ref "U5") (pin "14") (pinfunction "OUT3_14") (pintype "output"))
      (node (ref "U6") (pin "11") (pinfunction "2C1_11") (pintype "input"))
    )
    (net (code "20") (name "/DSCH") (class "Default")
      (node (ref "C19") (pin "1") (pinfunction "1_1") (pintype "passive"))
      (node (ref "R29") (pin "2") (pinfunction "2_2") (pintype "passive"))
    )
    (net (code "21") (name "/DUP") (class "Default")
      (node (ref "U5") (pin "1") (pinfunction "OUT2_1") (pintype "output"))
      (node (ref "U6") (pin "12") (pinfunction "2C2_12") (pintype "input"))
    )
    (net (code "22") (name "/ECHO") (class "Default")
      (node (ref "J1") (pin "2") (pinfunction "2_2") (pintype "passive"))
      (node (ref "U12") (pin "5") (pinfunction "IN1(+)_5") (pintype "input"))
    )
    (net (code "23") (name "/IMUXA") (class "Default")
      (node (ref "U1") (pin "13") (pinfunction "PD7(PCINT23/AIN1)_13") (pintype "bidirectional"))
      (node (ref "U6") (pin "14") (pinfunction "A_14") (pintype "input"))
    )
    (net (code "24") (name "/IMUXB") (class "Default")
      (node (ref "U1") (pin "14") (pinfunction "PB0(PCINT0/CLKO/ICP1)_14") (pintype "bidirectional"))
      (node (ref "U6") (pin "2") (pinfunction "B_2") (pintype "input"))
    )
    (net (code "25") (name "/INC") (class "Default")
      (node (ref "U11") (pin "3") (pinfunction "1Y_3") (pintype "output"))
      (node (ref "U2") (pin "1") (pinfunction "1CLK_1") (pintype "input"))
      (node (ref "U2") (pin "12") (pinfunction "2CLR_12") (pintype "input"))
      (node (ref "U9") (pin "8") (pinfunction "4Y_8") (pintype "bidirectional"))
    )
    (net (code "26") (name "/INPUT") (class "Default")
      (node (ref "U1") (pin "4") (pinfunction "PD2(PCINT18/INT0)_4") (pintype "bidirectional"))
      (node (ref "U7") (pin "7") (pinfunction "1Y_7") (pintype "output"))
    )
    (net (code "27") (name "/JOYSTICKOUT") (class "Default")
      (node (ref "U6") (pin "9") (pinfunction "2Y_9") (pintype "output"))
      (node (ref "U7") (pin "4") (pinfunction "1C2_4") (pintype "input"))
    )
    (net (code "28") (name "/LED1") (class "Default")
      (node (ref "R31") (pin "1") (pinfunction "1_1") (pintype "passive"))
      (node (ref "U10") (pin "3") (pinfunction "1Y_3") (pintype "output"))
    )
    (net (code "29") (name "/LED1A") (class "Default")
      (node (ref "J6") (pin "6") (pinfunction "6_6") (pintype "passive"))
      (node (ref "R6") (pin "2") (pinfunction "2_2") (pintype "passive"))
    )
    (net (code "30") (name "/LED1B") (class "Default")
      (node (ref "J6") (pin "8") (pinfunction "8_8") (pintype "passive"))
      (node (ref "R7") (pin "2") (pinfunction "2_2") (pintype "passive"))
    )
    (net (code "31") (name "/LED1C") (class "Default")
      (node (ref "J6") (pin "5") (pinfunction "5_5") (pintype "passive"))
      (node (ref "R8") (pin "2") (pinfunction "2_2") (pintype "passive"))
    )
    (net (code "32") (name "/LED1D") (class "Default")
      (node (ref "J6") (pin "3") (pinfunction "3_3") (pintype "passive"))
      (node (ref "R9") (pin "2") (pinfunction "2_2") (pintype "passive"))
    )
    (net (code "33") (name "/LED1E") (class "Default")
      (node (ref "J6") (pin "1") (pinfunction "1_1") (pintype "passive"))
      (node (ref "R10") (pin "2") (pinfunction "2_2") (pintype "passive"))
    )
    (net (code "34") (name "/LED1F") (class "Default")
      (node (ref "J6") (pin "2") (pinfunction "2_2") (pintype "passive"))
      (node (ref "R11") (pin "2") (pinfunction "2_2") (pintype "passive"))
    )
    (net (code "35") (name "/LED1G") (class "Default")
      (node (ref "J6") (pin "4") (pinfunction "4_4") (pintype "passive"))
      (node (ref "R12") (pin "2") (pinfunction "2_2") (pintype "passive"))
    )
    (net (code "36") (name "/LED2") (class "Default")
      (node (ref "R32") (pin "1") (pinfunction "1_1") (pintype "passive"))
      (node (ref "U10") (pin "6") (pinfunction "2Y_6") (pintype "output"))
    )
    (net (code "37") (name "/LED2A") (class "Default")
      (node (ref "J6") (pin "16") (pinfunction "16_16") (pintype "passive"))
      (node (ref "R13") (pin "2") (pinfunction "2_2") (pintype "passive"))
    )
    (net (code "38") (name "/LED2B") (class "Default")
      (node (ref "J6") (pin "18") (pinfunction "18_18") (pintype "passive"))
      (node (ref "R14") (pin "2") (pinfunction "2_2") (pintype "passive"))
    )
    (net (code "39") (name "/LED2C") (class "Default")
      (node (ref "J6") (pin "15") (pinfunction "15_15") (pintype "passive"))
      (node (ref "R15") (pin "2") (pinfunction "2_2") (pintype "passive"))
    )
    (net (code "40") (name "/LED2D") (class "Default")
      (node (ref "J6") (pin "11") (pinfunction "11_11") (pintype "passive"))
      (node (ref "R16") (pin "2") (pinfunction "2_2") (pintype "passive"))
    )
    (net (code "41") (name "/LED2E") (class "Default")
      (node (ref "J6") (pin "9") (pinfunction "9_9") (pintype "passive"))
      (node (ref "R17") (pin "2") (pinfunction "2_2") (pintype "passive"))
    )
    (net (code "42") (name "/LED2F") (class "Default")
      (node (ref "J6") (pin "14") (pinfunction "14_14") (pintype "passive"))
      (node (ref "R18") (pin "2") (pinfunction "2_2") (pintype "passive"))
    )
    (net (code "43") (name "/LED2G") (class "Default")
      (node (ref "J6") (pin "13") (pinfunction "13_13") (pintype "passive"))
      (node (ref "R19") (pin "2") (pinfunction "2_2") (pintype "passive"))
    )
    (net (code "44") (name "/LED3") (class "Default")
      (node (ref "R33") (pin "1") (pinfunction "1_1") (pintype "passive"))
      (node (ref "U10") (pin "8") (pinfunction "3Y_8") (pintype "output"))
    )
    (net (code "45") (name "/LED4") (class "Default")
      (node (ref "R34") (pin "1") (pinfunction "1_1") (pintype "passive"))
      (node (ref "U10") (pin "11") (pinfunction "4Y_11") (pintype "output"))
    )
    (net (code "46") (name "/LEFT") (class "Default")
      (node (ref "P1") (pin "2") (pinfunction "2_2") (pintype "passive"))
      (node (ref "R23") (pin "2") (pinfunction "2_2") (pintype "passive"))
      (node (ref "U5") (pin "11") (pinfunction "IN4(+)_11") (pintype "input"))
    )
    (net (code "47") (name "/Logical 0") (class "Default")
      (node (ref "R5") (pin "2") (pinfunction "2_2") (pintype "passive"))
      (node (ref "U3") (pin "5") (pinfunction "LE/!STORE_5") (pintype "bidirectional"))
      (node (ref "U4") (pin "5") (pinfunction "LE/!STORE_5") (pintype "bidirectional"))
    )
    (net (code "48") (name "/Logical 1") (class "Default")
      (node (ref "U3") (pin "3") (pinfunction "~{LT}_3") (pintype "bidirectional"))
      (node (ref "U3") (pin "4") (pinfunction "~{BL}_4") (pintype "bidirectional"))
    )
    (net (code "49") (name "/PB3") (class "Default")
      (node (ref "J4") (pin "02") (pinfunction "02_02") (pintype "passive"))
      (node (ref "SW1") (pin "1.1") (pinfunction "1.1_1.1") (pintype "passive"))
    )
    (net (code "50") (name "/PB4") (class "Default")
      (node (ref "J4") (pin "10") (pinfunction "10_10") (pintype "passive"))
      (node (ref "SW1") (pin "2.1") (pinfunction "2.1_2.1") (pintype "passive"))
    )
    (net (code "51") (name "/PB5") (class "Default")
      (node (ref "J4") (pin "08") (pinfunction "08_08") (pintype "passive"))
      (node (ref "SW1") (pin "3.1") (pinfunction "3.1_3.1") (pintype "passive"))
    )
    (net (code "52") (name "/PC6") (class "Default")
      (node (ref "J4") (pin "06") (pinfunction "06_06") (pintype "passive"))
      (node (ref "SW1") (pin "4.1") (pinfunction "4.1_4.1") (pintype "passive"))
    )
    (net (code "53") (name "/PULLUP1") (class "Default")
      (node (ref "R4") (pin "2") (pinfunction "2_2") (pintype "passive"))
      (node (ref "U4") (pin "3") (pinfunction "~{LT}_3") (pintype "bidirectional"))
      (node (ref "U4") (pin "4") (pinfunction "~{BL}_4") (pintype "bidirectional"))
      (node (ref "U7") (pin "15") (pinfunction "2~G_15") (pintype "input"))
    )
    (net (code "54") (name "/RESET") (class "Default")
      (node (ref "J5") (pin "2") (pinfunction "2_2") (pintype "passive"))
      (node (ref "R1") (pin "2") (pinfunction "2_2") (pintype "passive"))
      (node (ref "SW1") (pin "4.2") (pinfunction "4.2_4.2") (pintype "passive"))
      (node (ref "U1") (pin "1") (pinfunction "PC6(PCINT14/~{RESET})_1") (pintype "bidirectional"))
      (node (ref "U9") (pin "5") (pinfunction "3A_5") (pintype "bidirectional"))
      (node (ref "U9") (pin "9") (pinfunction "4A_9") (pintype "bidirectional"))
    )
    (net (code "55") (name "/RIGHT") (class "Default")
      (node (ref "P1") (pin "6") (pinfunction "6_6") (pintype "passive"))
      (node (ref "R22") (pin "2") (pinfunction "2_2") (pintype "passive"))
      (node (ref "U5") (pin "9") (pinfunction "IN3(+)_9") (pintype "input"))
    )
    (net (code "56") (name "/RST7") (class "Default")
      (node (ref "U2") (pin "2") (pinfunction "1CLR_2") (pintype "input"))
      (node (ref "U9") (pin "6") (pinfunction "3Y_6") (pintype "bidirectional"))
    )
    (net (code "57") (name "/SCORE") (class "Default")
      (node (ref "SW1") (pin "1.2") (pinfunction "1.2_1.2") (pintype "passive"))
      (node (ref "U1") (pin "17") (pinfunction "PB3(MOSI/OC2A/PCINT3)_17") (pintype "bidirectional"))
      (node (ref "U2") (pin "13") (pinfunction "2CLK_13") (pintype "input"))
    )
    (net (code "58") (name "/SPKR") (class "Default")
      (node (ref "R36") (pin "1") (pinfunction "1_1") (pintype "passive"))
      (node (ref "U1") (pin "16") (pinfunction "PB2(~{SS}/OC1B/PCINT2)_16") (pintype "bidirectional"))
    )
    (net (code "59") (name "/TRIG") (class "Default")
      (node (ref "J1") (pin "3") (pinfunction "3_3") (pintype "passive"))
      (node (ref "U8") (pin "3") (pinfunction "OUT_3") (pintype "output"))
    )
    (net (code "60") (name "/UP") (class "Default")
      (node (ref "P1") (pin "1") (pinfunction "1_1") (pintype "passive"))
      (node (ref "R21") (pin "2") (pinfunction "2_2") (pintype "passive"))
      (node (ref "U5") (pin "7") (pinfunction "IN2(+)_7") (pintype "input"))
    )
    (net (code "61") (name "/XTAL1") (class "Default")
      (node (ref "C8") (pin "1") (pinfunction "1_1") (pintype "passive"))
      (node (ref "U1") (pin "9") (pinfunction "PB6(PCINT6/XTAL1/TOSC1)_9") (pintype "bidirectional"))
      (node (ref "Y1") (pin "2") (pinfunction "OUT/IN_2") (pintype "passive"))
    )
    (net (code "62") (name "/XTAL2") (class "Default")
      (node (ref "C9") (pin "1") (pinfunction "1_1") (pintype "passive"))
      (node (ref "U1") (pin "10") (pinfunction "PB7(PCINT7/XTAL2/TOSC2)_10") (pintype "bidirectional"))
      (node (ref "Y1") (pin "1") (pinfunction "IN/OUT_1") (pintype "passive"))
    )
    (net (code "63") (name "GND") (class "Default")
      (node (ref "C0") (pin "2") (pinfunction "2_2") (pintype "passive"))
      (node (ref "C1") (pin "2") (pinfunction "2_2") (pintype "passive"))
      (node (ref "C10") (pin "2") (pinfunction "2_2") (pintype "passive"))
      (node (ref "C11") (pin "2") (pinfunction "2_2") (pintype "passive"))
      (node (ref "C12") (pin "2") (pinfunction "2_2") (pintype "passive"))
      (node (ref "C13") (pin "2") (pinfunction "2_2") (pintype "passive"))
      (node (ref "C14") (pin "2") (pinfunction "2_2") (pintype "passive"))
      (node (ref "C15") (pin "2") (pinfunction "2_2") (pintype "passive"))
      (node (ref "C16") (pin "2") (pinfunction "2_2") (pintype "passive"))
      (node (ref "C17") (pin "2") (pinfunction "2_2") (pintype "passive"))
      (node (ref "C2") (pin "2") (pinfunction "2_2") (pintype "passive"))
      (node (ref "C20") (pin "1") (pinfunction "1_1") (pintype "passive"))
      (node (ref "C21") (pin "1") (pinfunction "1_1") (pintype "passive"))
      (node (ref "C22") (pin "1") (pinfunction "1_1") (pintype "passive"))
      (node (ref "C23") (pin "1") (pinfunction "1_1") (pintype "passive"))
      (node (ref "C3") (pin "2") (pinfunction "2_2") (pintype "passive"))
      (node (ref "C4") (pin "2") (pinfunction "2_2") (pintype "passive"))
      (node (ref "C5") (pin "2") (pinfunction "2_2") (pintype "passive"))
      (node (ref "C6") (pin "2") (pinfunction "2_2") (pintype "passive"))
      (node (ref "C8") (pin "2") (pinfunction "2_2") (pintype "passive"))
      (node (ref "C9") (pin "2") (pinfunction "2_2") (pintype "passive"))
      (node (ref "J1") (pin "1") (pinfunction "1_1") (pintype "passive"))
      (node (ref "J2") (pin "A12") (pinfunction "GND_A12") (pintype "power_in"))
      (node (ref "J2") (pin "B12") (pinfunction "GND_B12") (pintype "power_in"))
      (node (ref "J2") (pin "S1") (pinfunction "SHIELD_S1") (pintype "passive"))
      (node (ref "J2") (pin "S2") (pinfunction "SHIELD_S2") (pintype "passive"))
      (node (ref "J4") (pin "03") (pinfunction "03_03") (pintype "passive"))
      (node (ref "J4") (pin "05") (pinfunction "05_05") (pintype "passive"))
      (node (ref "J4") (pin "07") (pinfunction "07_07") (pintype "passive"))
      (node (ref "J4") (pin "09") (pinfunction "09_09") (pintype "passive"))
      (node (ref "J5") (pin "1") (pinfunction "1_1") (pintype "passive"))
      (node (ref "J6") (pin "10") (pinfunction "10_10") (pintype "passive"))
      (node (ref "J6") (pin "12") (pinfunction "12_12") (pintype "passive"))
      (node (ref "LS1") (pin "N") (pinfunction "N_N") (pintype "passive"))
      (node (ref "P1") (pin "3") (pinfunction "3_3") (pintype "passive"))
      (node (ref "P1") (pin "4") (pinfunction "4_4") (pintype "passive"))
      (node (ref "P3 (LED)") (pin "3") (pinfunction "3_3") (pintype "passive"))
      (node (ref "P3 (LED)") (pin "4") (pinfunction "4_4") (pintype "passive"))
      (node (ref "P3 (LED)") (pin "7") (pinfunction "7_7") (pintype "passive"))
      (node (ref "P3 (LED)") (pin "8") (pinfunction "8_8") (pintype "passive"))
      (node (ref "R2") (pin "1") (pinfunction "1_1") (pintype "passive"))
      (node (ref "R24") (pin "1") (pinfunction "1_1") (pintype "passive"))
      (node (ref "R25") (pin "1") (pinfunction "1_1") (pintype "passive"))
      (node (ref "R26") (pin "1") (pinfunction "1_1") (pintype "passive"))
      (node (ref "R27") (pin "1") (pinfunction "1_1") (pintype "passive"))
      (node (ref "R3") (pin "1") (pinfunction "1_1") (pintype "passive"))
      (node (ref "R5") (pin "1") (pinfunction "1_1") (pintype "passive"))
      (node (ref "RV1") (pin "3") (pinfunction "3_3") (pintype "passive"))
      (node (ref "RV2") (pin "3") (pinfunction "3_3") (pintype "passive"))
      (node (ref "U1") (pin "22") (pinfunction "GND_22") (pintype "power_in"))
      (node (ref "U1") (pin "8") (pinfunction "GND_8") (pintype "power_in"))
      (node (ref "U10") (pin "7") (pinfunction "GND_7") (pintype "power_in"))
      (node (ref "U11") (pin "7") (pinfunction "GND_7") (pintype "power_in"))
      (node (ref "U12") (pin "12") (pinfunction "GND_12") (pintype "passive"))
      (node (ref "U2") (pin "7") (pinfunction "GND_7") (pintype "power_in"))
      (node (ref "U3") (pin "8") (pinfunction "VSS_8") (pintype "power_in"))
      (node (ref "U4") (pin "8") (pinfunction "VSS_8") (pintype "power_in"))
      (node (ref "U5") (pin "12") (pinfunction "GND_12") (pintype "passive"))
      (node (ref "U6") (pin "1") (pinfunction "1~G_1") (pintype "input"))
      (node (ref "U6") (pin "15") (pinfunction "2~G_15") (pintype "input"))
      (node (ref "U6") (pin "8") (pinfunction "GND_8") (pintype "power_in"))
      (node (ref "U7") (pin "1") (pinfunction "1~G_1") (pintype "input"))
      (node (ref "U7") (pin "10") (pinfunction "2C0_10") (pintype "input"))
      (node (ref "U7") (pin "11") (pinfunction "2C1_11") (pintype "input"))
      (node (ref "U7") (pin "12") (pinfunction "2C2_12") (pintype "input"))
      (node (ref "U7") (pin "13") (pinfunction "2C3_13") (pintype "input"))
      (node (ref "U7") (pin "6") (pinfunction "1C0_6") (pintype "input"))
      (node (ref "U7") (pin "8") (pinfunction "GND_8") (pintype "power_in"))
      (node (ref "U8") (pin "1") (pinfunction "GND_1") (pintype "power_in"))
      (node (ref "U9") (pin "7") (pinfunction "GND_7") (pintype "power_in"))
    )
    (net (code "64") (name "Net-(J2-CC1)") (class "Default")
      (node (ref "J2") (pin "A5") (pinfunction "CC1_A5") (pintype "passive"))
      (node (ref "R2") (pin "2") (pinfunction "2_2") (pintype "passive"))
    )
    (net (code "65") (name "Net-(J2-CC2)") (class "Default")
      (node (ref "J2") (pin "B5") (pinfunction "CC2_B5") (pintype "passive"))
      (node (ref "R3") (pin "2") (pinfunction "2_2") (pintype "passive"))
    )
    (net (code "66") (name "Net-(J2-VBUS-PadA9)") (class "Default")
      (node (ref "J2") (pin "A9") (pinfunction "VBUS_A9") (pintype "power_in"))
      (node (ref "J2") (pin "B9") (pinfunction "VBUS_B9") (pintype "power_in"))
      (node (ref "J3") (pin "2") (pinfunction "2_2") (pintype "passive"))
    )
    (net (code "67") (name "Net-(LS1-PadP)") (class "Default")
      (node (ref "LS1") (pin "P") (pinfunction "P_P") (pintype "passive"))
      (node (ref "R36") (pin "2") (pinfunction "2_2") (pintype "passive"))
    )
    (net (code "68") (name "Net-(P3 (LED)-Pad1)") (class "Default")
      (node (ref "P3 (LED)") (pin "1") (pinfunction "1_1") (pintype "passive"))
      (node (ref "R31") (pin "2") (pinfunction "2_2") (pintype "passive"))
    )
    (net (code "69") (name "Net-(P3 (LED)-Pad2)") (class "Default")
      (node (ref "P3 (LED)") (pin "2") (pinfunction "2_2") (pintype "passive"))
      (node (ref "R34") (pin "2") (pinfunction "2_2") (pintype "passive"))
    )
    (net (code "70") (name "Net-(P3 (LED)-Pad5)") (class "Default")
      (node (ref "P3 (LED)") (pin "5") (pinfunction "5_5") (pintype "passive"))
      (node (ref "R32") (pin "2") (pinfunction "2_2") (pintype "passive"))
    )
    (net (code "71") (name "Net-(P3 (LED)-Pad6)") (class "Default")
      (node (ref "P3 (LED)") (pin "6") (pinfunction "6_6") (pintype "passive"))
      (node (ref "R33") (pin "2") (pinfunction "2_2") (pintype "passive"))
    )
    (net (code "72") (name "Net-(U1-AREF)") (class "Default")
      (node (ref "C5") (pin "1") (pinfunction "1_1") (pintype "passive"))
      (node (ref "U1") (pin "21") (pinfunction "AREF_21") (pintype "input"))
    )
    (net (code "73") (name "Net-(U2-1QA)") (class "Default")
      (node (ref "U2") (pin "3") (pinfunction "1QA_3") (pintype "output"))
      (node (ref "U3") (pin "7") (pinfunction "LATCH_A_7") (pintype "input"))
    )
    (net (code "74") (name "Net-(U2-1QB)") (class "Default")
      (node (ref "U2") (pin "4") (pinfunction "1QB_4") (pintype "output"))
      (node (ref "U3") (pin "1") (pinfunction "LATCH_B_1") (pintype "input"))
    )
    (net (code "75") (name "Net-(U2-1QC)") (class "Default")
      (node (ref "U2") (pin "5") (pinfunction "1QC_5") (pintype "output"))
      (node (ref "U3") (pin "2") (pinfunction "LATCH_C_2") (pintype "input"))
    )
    (net (code "76") (name "Net-(U2-1QD)") (class "Default")
      (node (ref "U2") (pin "6") (pinfunction "1QD_6") (pintype "output"))
      (node (ref "U3") (pin "6") (pinfunction "LATCH_D_6") (pintype "input"))
    )
    (net (code "77") (name "Net-(U2-2QA)") (class "Default")
      (node (ref "U2") (pin "11") (pinfunction "2QA_11") (pintype "output"))
      (node (ref "U4") (pin "7") (pinfunction "LATCH_A_7") (pintype "input"))
    )
    (net (code "78") (name "Net-(U2-2QC)") (class "Default")
      (node (ref "U2") (pin "9") (pinfunction "2QC_9") (pintype "output"))
      (node (ref "U4") (pin "2") (pinfunction "LATCH_C_2") (pintype "input"))
    )
    (net (code "79") (name "Net-(U3-DRIVER_A)") (class "Default")
      (node (ref "R6") (pin "1") (pinfunction "1_1") (pintype "passive"))
      (node (ref "U3") (pin "13") (pinfunction "DRIVER_A_13") (pintype "output"))
    )
    (net (code "80") (name "Net-(U3-DRIVER_B)") (class "Default")
      (node (ref "R7") (pin "1") (pinfunction "1_1") (pintype "passive"))
      (node (ref "U3") (pin "12") (pinfunction "DRIVER_B_12") (pintype "output"))
    )
    (net (code "81") (name "Net-(U3-DRIVER_C)") (class "Default")
      (node (ref "R8") (pin "1") (pinfunction "1_1") (pintype "passive"))
      (node (ref "U3") (pin "11") (pinfunction "DRIVER_C_11") (pintype "output"))
    )
    (net (code "82") (name "Net-(U3-DRIVER_D)") (class "Default")
      (node (ref "R9") (pin "1") (pinfunction "1_1") (pintype "passive"))
      (node (ref "U3") (pin "10") (pinfunction "DRIVER_D_10") (pintype "output"))
    )
    (net (code "83") (name "Net-(U3-DRIVER_E)") (class "Default")
      (node (ref "R10") (pin "1") (pinfunction "1_1") (pintype "passive"))
      (node (ref "U3") (pin "9") (pinfunction "DRIVER_E_9") (pintype "output"))
    )
    (net (code "84") (name "Net-(U3-DRIVER_F)") (class "Default")
      (node (ref "R11") (pin "1") (pinfunction "1_1") (pintype "passive"))
      (node (ref "U3") (pin "15") (pinfunction "DRIVER_F_15") (pintype "output"))
    )
    (net (code "85") (name "Net-(U3-DRIVER_G)") (class "Default")
      (node (ref "R12") (pin "1") (pinfunction "1_1") (pintype "passive"))
      (node (ref "U3") (pin "14") (pinfunction "DRIVER_G_14") (pintype "output"))
    )
    (net (code "86") (name "Net-(U4-DRIVER_A)") (class "Default")
      (node (ref "R13") (pin "1") (pinfunction "1_1") (pintype "passive"))
      (node (ref "U4") (pin "13") (pinfunction "DRIVER_A_13") (pintype "output"))
    )
    (net (code "87") (name "Net-(U4-DRIVER_B)") (class "Default")
      (node (ref "R14") (pin "1") (pinfunction "1_1") (pintype "passive"))
      (node (ref "U4") (pin "12") (pinfunction "DRIVER_B_12") (pintype "output"))
    )
    (net (code "88") (name "Net-(U4-DRIVER_C)") (class "Default")
      (node (ref "R15") (pin "1") (pinfunction "1_1") (pintype "passive"))
      (node (ref "U4") (pin "11") (pinfunction "DRIVER_C_11") (pintype "output"))
    )
    (net (code "89") (name "Net-(U4-DRIVER_D)") (class "Default")
      (node (ref "R16") (pin "1") (pinfunction "1_1") (pintype "passive"))
      (node (ref "U4") (pin "10") (pinfunction "DRIVER_D_10") (pintype "output"))
    )
    (net (code "90") (name "Net-(U4-DRIVER_E)") (class "Default")
      (node (ref "R17") (pin "1") (pinfunction "1_1") (pintype "passive"))
      (node (ref "U4") (pin "9") (pinfunction "DRIVER_E_9") (pintype "output"))
    )
    (net (code "91") (name "Net-(U4-DRIVER_F)") (class "Default")
      (node (ref "R18") (pin "1") (pinfunction "1_1") (pintype "passive"))
      (node (ref "U4") (pin "15") (pinfunction "DRIVER_F_15") (pintype "output"))
    )
    (net (code "92") (name "Net-(U4-DRIVER_G)") (class "Default")
      (node (ref "R19") (pin "1") (pinfunction "1_1") (pintype "passive"))
      (node (ref "U4") (pin "14") (pinfunction "DRIVER_G_14") (pintype "output"))
    )
    (net (code "93") (name "Net-(U5-IN1(-))") (class "Default")
      (node (ref "RV1") (pin "2") (pinfunction "2_2") (pintype "passive"))
      (node (ref "U5") (pin "10") (pinfunction "IN4(-)_10") (pintype "input"))
      (node (ref "U5") (pin "4") (pinfunction "IN1(-)_4") (pintype "input"))
      (node (ref "U5") (pin "6") (pinfunction "IN2(-)_6") (pintype "input"))
      (node (ref "U5") (pin "8") (pinfunction "IN3(-)_8") (pintype "input"))
    )
    (net (code "94") (name "Net-(U8-CONT)") (class "Default")
      (node (ref "C18") (pin "1") (pinfunction "1_1") (pintype "passive"))
      (node (ref "U8") (pin "5") (pinfunction "CONT_5") (pintype "bidirectional"))
    )
    (net (code "95") (name "Net-(U8-DISCH)") (class "Default")
      (node (ref "R28") (pin "1") (pinfunction "1_1") (pintype "passive"))
      (node (ref "R29") (pin "1") (pinfunction "1_1") (pintype "passive"))
      (node (ref "U8") (pin "7") (pinfunction "DISCH_7") (pintype "output"))
    )
    (net (code "96") (name "Net-(U8-THRES)") (class "Default")
      (node (ref "C19") (pin "2") (pinfunction "2_2") (pintype "passive"))
      (node (ref "U8") (pin "2") (pinfunction "TRIG_2") (pintype "input"))
      (node (ref "U8") (pin "6") (pinfunction "THRES_6") (pintype "input"))
    )
    (net (code "97") (name "Net-(U9-5A)") (class "Default")
      (node (ref "R30") (pin "1") (pinfunction "1_1") (pintype "passive"))
      (node (ref "U9") (pin "11") (pinfunction "5A_11") (pintype "bidirectional"))
      (node (ref "U9") (pin "13") (pinfunction "6A_13") (pintype "bidirectional"))
    )
    (net (code "98") (name "Net-(U11-2A)") (class "Default")
      (node (ref "R35") (pin "1") (pinfunction "1_1") (pintype "passive"))
      (node (ref "U11") (pin "10") (pinfunction "3B_10") (pintype "input"))
      (node (ref "U11") (pin "12") (pinfunction "4A_12") (pintype "input"))
      (node (ref "U11") (pin "13") (pinfunction "4B_13") (pintype "input"))
      (node (ref "U11") (pin "4") (pinfunction "2A_4") (pintype "input"))
      (node (ref "U11") (pin "5") (pinfunction "2B_5") (pintype "input"))
      (node (ref "U11") (pin "9") (pinfunction "3A_9") (pintype "input"))
    )
    (net (code "99") (name "Net-(U12-IN1(-))") (class "Default")
      (node (ref "RV2") (pin "2") (pinfunction "2_2") (pintype "passive"))
      (node (ref "U12") (pin "10") (pinfunction "IN4(-)_10") (pintype "input"))
      (node (ref "U12") (pin "4") (pinfunction "IN1(-)_4") (pintype "input"))
      (node (ref "U12") (pin "6") (pinfunction "IN2(-)_6") (pintype "input"))
      (node (ref "U12") (pin "8") (pinfunction "IN3(-)_8") (pintype "input"))
    )
    (net (code "100") (name "Net-(U12-IN2(+))") (class "Default")
      (node (ref "R37") (pin "1") (pinfunction "1_1") (pintype "passive"))
      (node (ref "U12") (pin "11") (pinfunction "IN4(+)_11") (pintype "input"))
      (node (ref "U12") (pin "7") (pinfunction "IN2(+)_7") (pintype "input"))
      (node (ref "U12") (pin "9") (pinfunction "IN3(+)_9") (pintype "input"))
    )
    (net (code "101") (name "unconnected-(C18-Pad2)") (class "Default")
      (node (ref "C18") (pin "2") (pinfunction "2_2") (pintype "passive"))
    )
    (net (code "102") (name "unconnected-(J4-Pad04)") (class "Default")
      (node (ref "J4") (pin "04") (pinfunction "04_04") (pintype "passive+no_connect"))
    )
    (net (code "103") (name "unconnected-(J6-Pad7)") (class "Default")
      (node (ref "J6") (pin "7") (pinfunction "7_7") (pintype "passive+no_connect"))
    )
    (net (code "104") (name "unconnected-(J6-Pad17)") (class "Default")
      (node (ref "J6") (pin "17") (pinfunction "17_17") (pintype "passive+no_connect"))
    )
    (net (code "105") (name "unconnected-(U1-PB1(OC1A{slash}PCINT1)-Pad15)") (class "Default")
      (node (ref "U1") (pin "15") (pinfunction "PB1(OC1A/PCINT1)_15") (pintype "bidirectional"))
    )
    (net (code "106") (name "unconnected-(U1-PC0(ADC0{slash}PCINT8)-Pad23)") (class "Default")
      (node (ref "U1") (pin "23") (pinfunction "PC0(ADC0/PCINT8)_23") (pintype "bidirectional"))
    )
    (net (code "107") (name "unconnected-(U1-PC1(ADC1{slash}PCINT9)-Pad24)") (class "Default")
      (node (ref "U1") (pin "24") (pinfunction "PC1(ADC1/PCINT9)_24") (pintype "bidirectional"))
    )
    (net (code "108") (name "unconnected-(U1-PC2(ADC2{slash}PCINT10)-Pad25)") (class "Default")
      (node (ref "U1") (pin "25") (pinfunction "PC2(ADC2/PCINT10)_25") (pintype "bidirectional"))
    )
    (net (code "109") (name "unconnected-(U1-PC3(ADC3{slash}PCINT11)-Pad26)") (class "Default")
      (node (ref "U1") (pin "26") (pinfunction "PC3(ADC3/PCINT11)_26") (pintype "bidirectional"))
    )
    (net (code "110") (name "unconnected-(U1-PC4(ADC4{slash}SDA{slash}PCINT12)-Pad27)") (class "Default")
      (node (ref "U1") (pin "27") (pinfunction "PC4(ADC4/SDA/PCINT12)_27") (pintype "bidirectional"))
    )
    (net (code "111") (name "unconnected-(U1-PC5(ADC5{slash}SCL{slash}PCINT13)-Pad28)") (class "Default")
      (node (ref "U1") (pin "28") (pinfunction "PC5(ADC5/SCL/PCINT13)_28") (pintype "bidirectional"))
    )
    (net (code "112") (name "unconnected-(U1-PD0(PCINT16{slash}RXD)-Pad2)") (class "Default")
      (node (ref "U1") (pin "2") (pinfunction "PD0(PCINT16/RXD)_2") (pintype "bidirectional"))
    )
    (net (code "113") (name "unconnected-(U1-PD1(PCINT17{slash}TXD)-Pad3)") (class "Default")
      (node (ref "U1") (pin "3") (pinfunction "PD1(PCINT17/TXD)_3") (pintype "bidirectional"))
    )
    (net (code "114") (name "unconnected-(U1-PD3(PCINT19{slash}OC2B{slash}INT1)-Pad5)") (class "Default")
      (node (ref "U1") (pin "5") (pinfunction "PD3(PCINT19/OC2B/INT1)_5") (pintype "bidirectional"))
    )
    (net (code "115") (name "unconnected-(U1-PD4(PCINT20{slash}XCK{slash}T0)-Pad6)") (class "Default")
      (node (ref "U1") (pin "6") (pinfunction "PD4(PCINT20/XCK/T0)_6") (pintype "bidirectional"))
    )
    (net (code "116") (name "unconnected-(U1-PD5(PCINT21{slash}OC0B{slash}T1)-Pad11)") (class "Default")
      (node (ref "U1") (pin "11") (pinfunction "PD5(PCINT21/OC0B/T1)_11") (pintype "bidirectional"))
    )
    (net (code "117") (name "unconnected-(U1-PD6(PCINT22{slash}OC0A{slash}AIN0)-Pad12)") (class "Default")
      (node (ref "U1") (pin "12") (pinfunction "PD6(PCINT22/OC0A/AIN0)_12") (pintype "bidirectional"))
    )
    (net (code "118") (name "unconnected-(U7-2Y-Pad9)") (class "Default")
      (node (ref "U7") (pin "9") (pinfunction "2Y_9") (pintype "output+no_connect"))
    )
    (net (code "119") (name "unconnected-(U9-5Y-Pad10)") (class "Default")
      (node (ref "U9") (pin "10") (pinfunction "5Y_10") (pintype "bidirectional+no_connect"))
    )
    (net (code "120") (name "unconnected-(U9-6Y-Pad12)") (class "Default")
      (node (ref "U9") (pin "12") (pinfunction "6Y_12") (pintype "bidirectional+no_connect"))
    )
    (net (code "121") (name "unconnected-(U11-2Y-Pad6)") (class "Default")
      (node (ref "U11") (pin "6") (pinfunction "2Y_6") (pintype "output+no_connect"))
    )
    (net (code "122") (name "unconnected-(U11-3Y-Pad8)") (class "Default")
      (node (ref "U11") (pin "8") (pinfunction "3Y_8") (pintype "output+no_connect"))
    )
    (net (code "123") (name "unconnected-(U11-4Y-Pad11)") (class "Default")
      (node (ref "U11") (pin "11") (pinfunction "4Y_11") (pintype "output+no_connect"))
    )
    (net (code "124") (name "unconnected-(U12-OUT2-Pad1)") (class "Default")
      (node (ref "U12") (pin "1") (pinfunction "OUT2_1") (pintype "output+no_connect"))
    )
    (net (code "125") (name "unconnected-(U12-OUT3-Pad14)") (class "Default")
      (node (ref "U12") (pin "14") (pinfunction "OUT3_14") (pintype "output+no_connect"))
    )
    (net (code "126") (name "unconnected-(U12-OUT4-Pad13)") (class "Default")
      (node (ref "U12") (pin "13") (pinfunction "OUT4_13") (pintype "output+no_connect"))
    )
  )
)
